# Connectors.net
KiCad netlist of a schematic drawn in Altium Designer
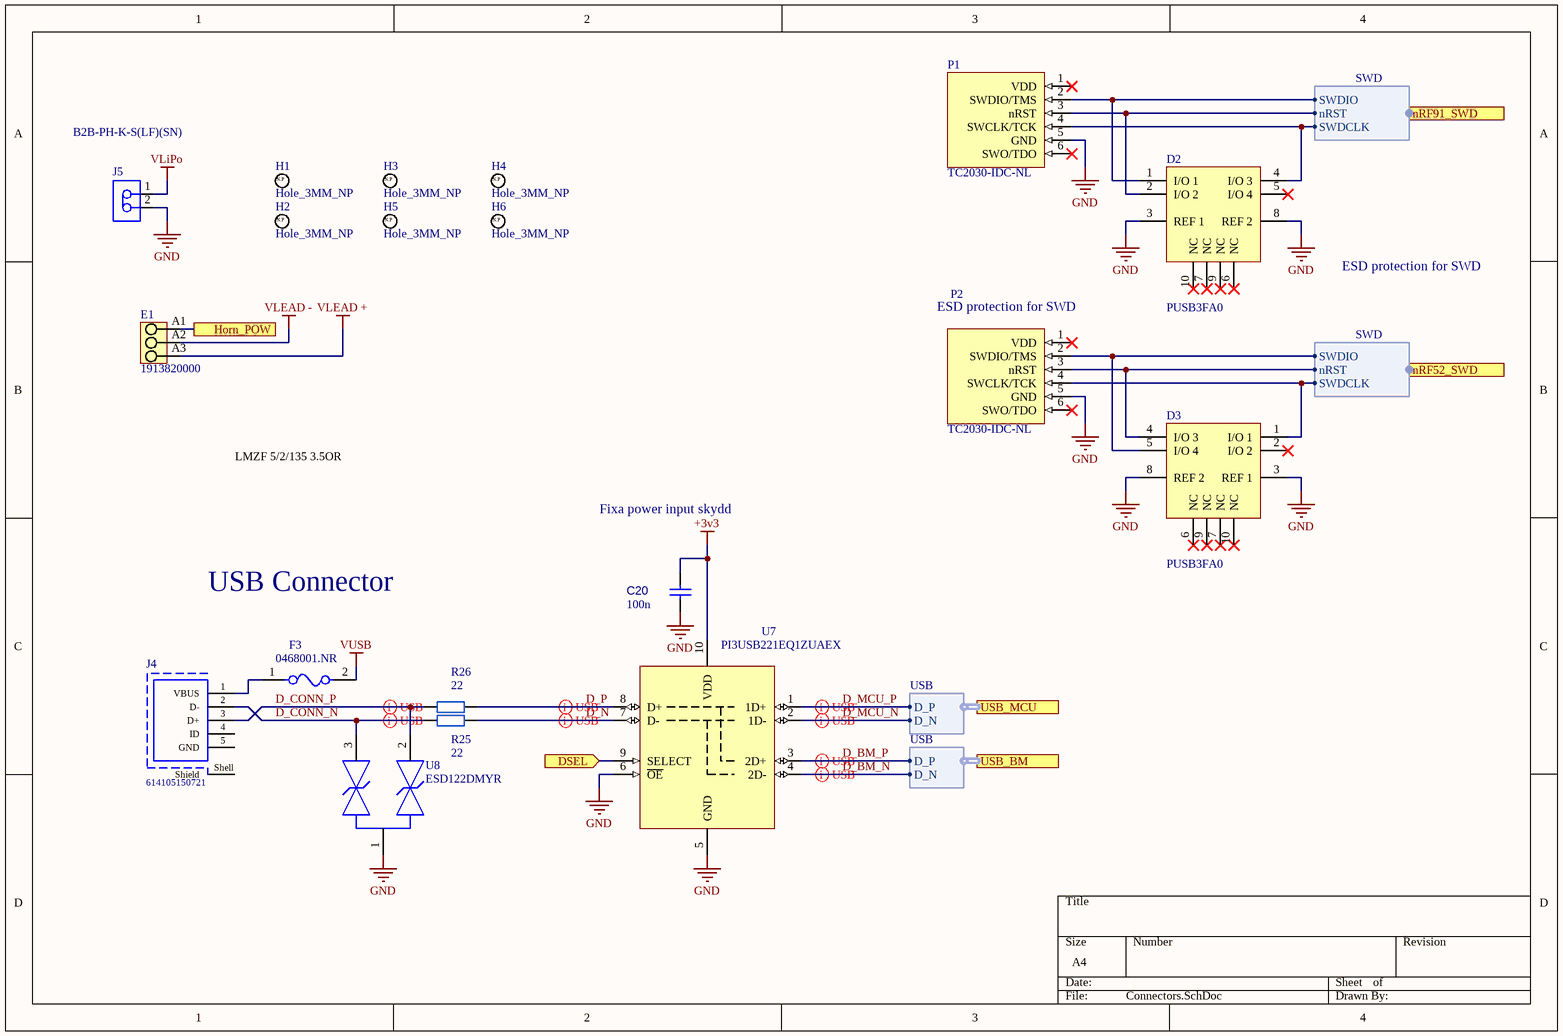
[diagram p0: Connectors.SchDoc]

(export (version "E")
  (design (tool "Eeschema 10.0.6"))
  (components
    (comp (ref "C20")
      (value "100n")
      (footprint "CAPC1005X55X25LL05T10 HD")
      (description "Chip Capacitor, 0402 (1005 Metric)")
      (fields (field (name "TOLERANCE") "?%") (field (name "Comment") "Capacitor 0402"))
      (libsource (lib "Motonaut") (part "CAP-NP-2"))
    )
    (comp (ref "D2")
      (value "PUSB3FA0")
      (footprint "FP-SOT1176-1-MFG")
      (description "ESD protection for ultra high-speed interfaces")
      (libsource (lib "Motonaut") (part "7af82cefb99888626757485c32e8fb9"))
    )
    (comp (ref "D3")
      (value "PUSB3FA0")
      (footprint "FP-SOT1176-1-MFG")
      (description "ESD protection for ultra high-speed interfaces")
      (libsource (lib "") (part "7af82cefb99888626757485c32e8fb9_1"))
    )
    (comp (ref "E1")
      (value "1913820000")
      (footprint "LMZF_5_135_03")
      (description "OMNIMATE Signal - series LMZF")
      (fields (field (name "MANUFACTURER") "Weidmueller"))
      (libsource (lib "Altium Content Vault") (part "Terminal_03_1x03"))
    )
    (comp (ref "F3")
      (value "0468001.NR")
      (footprint "FP-0468-MFG")
      (description "FUSE BOARD MNT 1A 63VAC/VDC 1206")
      (fields
        (field (name "MANUFACTURER") "Littelfuse")
        (field (name "OCTOPART") "https://octopart.com/0468001.nr-littelfuse-566477")
      )
      (libsource (lib "Altium Content Vault") (part "5bcf9b9f640e542cf0359d10258e979"))
    )
    (comp (ref "H1")
      (value "Hole_3MM_NP")
      (footprint "Hole_3MM_NP-Footprint-1")
      (description "Regular Non-Plated, 3mm hole")
      (fields
        (field (name "MANUFACTURER PART NUMBER") "N.A.")
        (field (name "MANUFACTURER") "Nordic Semiconductor")
      )
      (libsource (lib "Motonaut") (part "Hole_3MM_NP"))
    )
    (comp (ref "H2")
      (value "Hole_3MM_NP")
      (footprint "Hole_3MM_NP-Footprint-1")
      (description "Regular Non-Plated, 3mm hole")
      (fields
        (field (name "MANUFACTURER PART NUMBER") "N.A.")
        (field (name "MANUFACTURER") "Nordic Semiconductor")
      )
      (libsource (lib "Motonaut") (part "Hole_3MM_NP"))
    )
    (comp (ref "H3")
      (value "Hole_3MM_NP")
      (footprint "Hole_3MM_NP-Footprint-1")
      (description "Regular Non-Plated, 3mm hole")
      (fields
        (field (name "MANUFACTURER PART NUMBER") "N.A.")
        (field (name "MANUFACTURER") "Nordic Semiconductor")
      )
      (libsource (lib "Motonaut") (part "Hole_3MM_NP"))
    )
    (comp (ref "H4")
      (value "Hole_3MM_NP")
      (footprint "Hole_3MM_NP-Footprint-1")
      (description "Regular Non-Plated, 3mm hole")
      (fields
        (field (name "MANUFACTURER PART NUMBER") "N.A.")
        (field (name "MANUFACTURER") "Nordic Semiconductor")
      )
      (libsource (lib "Motonaut") (part "Hole_3MM_NP"))
    )
    (comp (ref "H5")
      (value "Hole_3MM_NP")
      (footprint "Hole_3MM_NP-Footprint-1")
      (description "Regular Non-Plated, 3mm hole")
      (fields
        (field (name "MANUFACTURER PART NUMBER") "N.A.")
        (field (name "MANUFACTURER") "Nordic Semiconductor")
      )
      (libsource (lib "Motonaut") (part "Hole_3MM_NP"))
    )
    (comp (ref "H6")
      (value "Hole_3MM_NP")
      (footprint "Hole_3MM_NP-Footprint-1")
      (description "Regular Non-Plated, 3mm hole")
      (fields
        (field (name "MANUFACTURER PART NUMBER") "N.A.")
        (field (name "MANUFACTURER") "Nordic Semiconductor")
      )
      (libsource (lib "Motonaut") (part "Hole_3MM_NP"))
    )
    (comp (ref "J4")
      (value "614105150721")
      (footprint "614105150721")
      (description "Micro USB 2.0 Type B Receptacle WR-COM, Vertical, THT")
      (fields (field (name "MANUFACTURER") "Wurth Elektronik") (field (name "PUBLISHER") "WurthElektronik"))
      (libsource (lib "Altium Content Vault") (part "WE-USB-5-1SHLD"))
    )
    (comp (ref "J5")
      (value "B2B-PH-K-S(LF)(SN)")
      (footprint "JST-B2B-PH-K-S_V")
      (fields (field (name "MANUFACTURER") "JST"))
      (libsource (lib "Altium Content Vault") (part "CN-2P-F-QF2"))
    )
    (comp (ref "P1")
      (value "TC2030-IDC-NL")
      (footprint "New footprint 1")
      (libsource (lib "Motonaut") (part "TC2030 6-pin Tag Connect"))
    )
    (comp (ref "P2")
      (value "TC2030-IDC-NL")
      (footprint "New footprint 1")
      (libsource (lib "Motonaut") (part "TC2030 6-pin Tag Connect"))
    )
    (comp (ref "R25")
      (value "22")
      (footprint "RESC1005X40X25LL10T10 HD")
      (description "Resistor 0403")
      (libsource (lib "Motonaut") (part "Resistor EU"))
    )
    (comp (ref "R26")
      (value "22")
      (footprint "RESC1005X40X25LL10T10 HD")
      (description "Resistor 0403")
      (libsource (lib "Motonaut") (part "Resistor EU"))
    )
    (comp (ref "U7")
      (value "PI3USB221EQ1ZUAEX")
      (footprint "PI3USB221EQ1ZUAEX-Footprint-1")
      (description "High-Speed USB2.0 1:2 Multiplexer/DeMultiplexer Switch with Signal Enable")
      (libsource (lib "Motonaut") (part "PI3USB221EQ1ZUAEX-Symbol-1"))
    )
    (comp (ref "U8")
      (value "ESD122DMYR")
      (footprint "FP-DMY0003A-MFG")
      (description "TVS DIODE 3.6V 8.4V 3X2SON")
      (libsource (lib "Altium Content Vault") (part "d1663bc381df522db30265c6c62fec7"))
    )
  )
  (nets
    (net (code "3") (name "+3v3") (class "Default")
      (node (ref "C20") (pin "2") (pinfunction "2_2") (pintype "passive"))
      (node (ref "U7") (pin "10") (pinfunction "VDD_10") (pintype "power_in"))
    )
    (net (code "5") (name "/DSEL") (class "Default")
      (node (ref "U7") (pin "9") (pinfunction "SELECT_9") (pintype "input"))
    )
    (net (code "6") (name "/D_BM_N") (class "Default")
      (node (ref "U7") (pin "4") (pinfunction "2D-_4") (pintype "bidirectional"))
    )
    (net (code "7") (name "/D_BM_P") (class "Default")
      (node (ref "U7") (pin "3") (pinfunction "2D+_3") (pintype "bidirectional"))
    )
    (net (code "8") (name "/D_CONN_N") (class "Default")
      (node (ref "J4") (pin "2") (pinfunction "D-_2") (pintype "passive"))
      (node (ref "R25") (pin "1") (pinfunction "1_1") (pintype "passive"))
      (node (ref "U8") (pin "3") (pinfunction "IO2_3") (pintype "passive"))
    )
    (net (code "9") (name "/D_CONN_P") (class "Default")
      (node (ref "J4") (pin "3") (pinfunction "D+_3") (pintype "passive"))
      (node (ref "R26") (pin "1") (pinfunction "1_1") (pintype "passive"))
      (node (ref "U8") (pin "2") (pinfunction "IO1_2") (pintype "passive"))
    )
    (net (code "10") (name "/D_MCU_N") (class "Default")
      (node (ref "U7") (pin "2") (pinfunction "1D-_2") (pintype "bidirectional"))
    )
    (net (code "11") (name "/D_MCU_P") (class "Default")
      (node (ref "U7") (pin "1") (pinfunction "1D+_1") (pintype "bidirectional"))
    )
    (net (code "12") (name "/D_N") (class "Default")
      (node (ref "R25") (pin "2") (pinfunction "2_2") (pintype "passive"))
      (node (ref "U7") (pin "7") (pinfunction "D-_7") (pintype "bidirectional"))
    )
    (net (code "13") (name "/D_P") (class "Default")
      (node (ref "R26") (pin "2") (pinfunction "2_2") (pintype "passive"))
      (node (ref "U7") (pin "8") (pinfunction "D+_8") (pintype "bidirectional"))
    )
    (net (code "14") (name "/Horn_POW") (class "Default")
      (node (ref "E1") (pin "A1") (pinfunction "A1_A1") (pintype "passive"))
    )
    (net (code "17") (name "GND") (class "Default")
      (node (ref "C20") (pin "1") (pinfunction "1_1") (pintype "passive"))
      (node (ref "D2") (pin "3") (pinfunction "REF_1_3") (pintype "passive"))
      (node (ref "D2") (pin "8") (pinfunction "REF_2_8") (pintype "passive"))
      (node (ref "D3") (pin "3") (pinfunction "REF_1_3") (pintype "passive"))
      (node (ref "D3") (pin "8") (pinfunction "REF_2_8") (pintype "passive"))
      (node (ref "J5") (pin "2") (pinfunction "2_2") (pintype "passive"))
      (node (ref "P1") (pin "5") (pinfunction "GND_5") (pintype "input"))
      (node (ref "P2") (pin "5") (pinfunction "GND_5") (pintype "input"))
      (node (ref "U7") (pin "5") (pinfunction "GND_5") (pintype "power_in"))
      (node (ref "U7") (pin "6") (pinfunction "~{OE}_6") (pintype "input"))
      (node (ref "U8") (pin "1") (pinfunction "GND_1") (pintype "power_in"))
    )
    (net (code "18") (name "Net-(D2-I{slash}O_1)") (class "Default")
      (node (ref "D2") (pin "1") (pinfunction "I/O_1_1") (pintype "passive"))
      (node (ref "P1") (pin "2") (pinfunction "SWDIO/TMS_2") (pintype "input"))
    )
    (net (code "19") (name "Net-(D2-I{slash}O_2)") (class "Default")
      (node (ref "D2") (pin "2") (pinfunction "I/O_2_2") (pintype "passive"))
      (node (ref "P1") (pin "3") (pinfunction "nRST_3") (pintype "input"))
    )
    (net (code "20") (name "Net-(D2-I{slash}O_3)") (class "Default")
      (node (ref "D2") (pin "4") (pinfunction "I/O_3_4") (pintype "passive"))
      (node (ref "P1") (pin "4") (pinfunction "SWCLK/TCK_4") (pintype "input"))
    )
    (net (code "21") (name "Net-(D3-I{slash}O_1)") (class "Default")
      (node (ref "D3") (pin "1") (pinfunction "I/O_1_1") (pintype "passive"))
      (node (ref "P2") (pin "4") (pinfunction "SWCLK/TCK_4") (pintype "input"))
    )
    (net (code "22") (name "Net-(D3-I{slash}O_3)") (class "Default")
      (node (ref "D3") (pin "4") (pinfunction "I/O_3_4") (pintype "passive"))
      (node (ref "P2") (pin "3") (pinfunction "nRST_3") (pintype "input"))
    )
    (net (code "23") (name "Net-(D3-I{slash}O_4)") (class "Default")
      (node (ref "D3") (pin "5") (pinfunction "I/O_4_5") (pintype "passive"))
      (node (ref "P2") (pin "2") (pinfunction "SWDIO/TMS_2") (pintype "input"))
    )
    (net (code "24") (name "Net-(J4-VBUS)") (class "Default")
      (node (ref "F3") (pin "1") (pinfunction "1_1") (pintype "passive"))
      (node (ref "J4") (pin "1") (pinfunction "VBUS_1") (pintype "passive"))
    )
    (net (code "25") (name "VLEAD +") (class "Default")
      (node (ref "E1") (pin "A3") (pinfunction "A3_A3") (pintype "passive"))
    )
    (net (code "26") (name "VLEAD -") (class "Default")
      (node (ref "E1") (pin "A2") (pinfunction "A2_A2") (pintype "passive"))
    )
    (net (code "27") (name "VLiPo") (class "Default")
      (node (ref "J5") (pin "1") (pinfunction "1_1") (pintype "passive"))
    )
    (net (code "28") (name "VUSB") (class "Default")
      (node (ref "F3") (pin "2") (pinfunction "2_2") (pintype "passive"))
    )
    (net (code "29") (name "unconnected-(D2-I{slash}O_4-Pad5)") (class "Default")
      (node (ref "D2") (pin "5") (pinfunction "I/O_4_5") (pintype "passive+no_connect"))
    )
    (net (code "30") (name "unconnected-(D2-NC-Pad6)") (class "Default")
      (node (ref "D2") (pin "6") (pinfunction "NC_6") (pintype "passive+no_connect"))
    )
    (net (code "31") (name "unconnected-(D2-NC-Pad7)") (class "Default")
      (node (ref "D2") (pin "7") (pinfunction "NC_7") (pintype "passive+no_connect"))
    )
    (net (code "32") (name "unconnected-(D2-NC-Pad9)") (class "Default")
      (node (ref "D2") (pin "9") (pinfunction "NC_9") (pintype "passive+no_connect"))
    )
    (net (code "33") (name "unconnected-(D2-NC-Pad10)") (class "Default")
      (node (ref "D2") (pin "10") (pinfunction "NC_10") (pintype "passive+no_connect"))
    )
    (net (code "34") (name "unconnected-(D3-I{slash}O_2-Pad2)") (class "Default")
      (node (ref "D3") (pin "2") (pinfunction "I/O_2_2") (pintype "passive+no_connect"))
    )
    (net (code "35") (name "unconnected-(D3-NC-Pad6)") (class "Default")
      (node (ref "D3") (pin "6") (pinfunction "NC_6") (pintype "passive+no_connect"))
    )
    (net (code "36") (name "unconnected-(D3-NC-Pad7)") (class "Default")
      (node (ref "D3") (pin "7") (pinfunction "NC_7") (pintype "passive+no_connect"))
    )
    (net (code "37") (name "unconnected-(D3-NC-Pad9)") (class "Default")
      (node (ref "D3") (pin "9") (pinfunction "NC_9") (pintype "passive+no_connect"))
    )
    (net (code "38") (name "unconnected-(D3-NC-Pad10)") (class "Default")
      (node (ref "D3") (pin "10") (pinfunction "NC_10") (pintype "passive+no_connect"))
    )
    (net (code "39") (name "unconnected-(H1-Pad1)") (class "Default")
      (node (ref "H1") (pin "1") (pinfunction "1_1") (pintype "passive"))
    )
    (net (code "40") (name "unconnected-(H2-Pad1)") (class "Default")
      (node (ref "H2") (pin "1") (pinfunction "1_1") (pintype "passive"))
    )
    (net (code "41") (name "unconnected-(H3-Pad1)") (class "Default")
      (node (ref "H3") (pin "1") (pinfunction "1_1") (pintype "passive"))
    )
    (net (code "42") (name "unconnected-(H4-Pad1)") (class "Default")
      (node (ref "H4") (pin "1") (pinfunction "1_1") (pintype "passive"))
    )
    (net (code "43") (name "unconnected-(H5-Pad1)") (class "Default")
      (node (ref "H5") (pin "1") (pinfunction "1_1") (pintype "passive"))
    )
    (net (code "44") (name "unconnected-(H6-Pad1)") (class "Default")
      (node (ref "H6") (pin "1") (pinfunction "1_1") (pintype "passive"))
    )
    (net (code "45") (name "unconnected-(J4-GND-Pad5)") (class "Default")
      (node (ref "J4") (pin "5") (pinfunction "GND_5") (pintype "passive"))
    )
    (net (code "46") (name "unconnected-(J4-ID-Pad4)") (class "Default")
      (node (ref "J4") (pin "4") (pinfunction "ID_4") (pintype "passive"))
    )
    (net (code "47") (name "unconnected-(J4-Shield-PadShell)") (class "Default")
      (node (ref "J4") (pin "Shell") (pinfunction "Shield_Shell") (pintype "passive"))
    )
    (net (code "48") (name "unconnected-(P1-SWO{slash}TDO-Pad6)") (class "Default")
      (node (ref "P1") (pin "6") (pinfunction "SWO/TDO_6") (pintype "input+no_connect"))
    )
    (net (code "49") (name "unconnected-(P1-VDD-Pad1)") (class "Default")
      (node (ref "P1") (pin "1") (pinfunction "VDD_1") (pintype "input+no_connect"))
    )
    (net (code "50") (name "unconnected-(P2-SWO{slash}TDO-Pad6)") (class "Default")
      (node (ref "P2") (pin "6") (pinfunction "SWO/TDO_6") (pintype "input+no_connect"))
    )
    (net (code "51") (name "unconnected-(P2-VDD-Pad1)") (class "Default")
      (node (ref "P2") (pin "1") (pinfunction "VDD_1") (pintype "input+no_connect"))
    )
  )
)
